# CHAIRCONTROLMOTORS.net
KiCad netlist of a schematic drawn in EAGLE
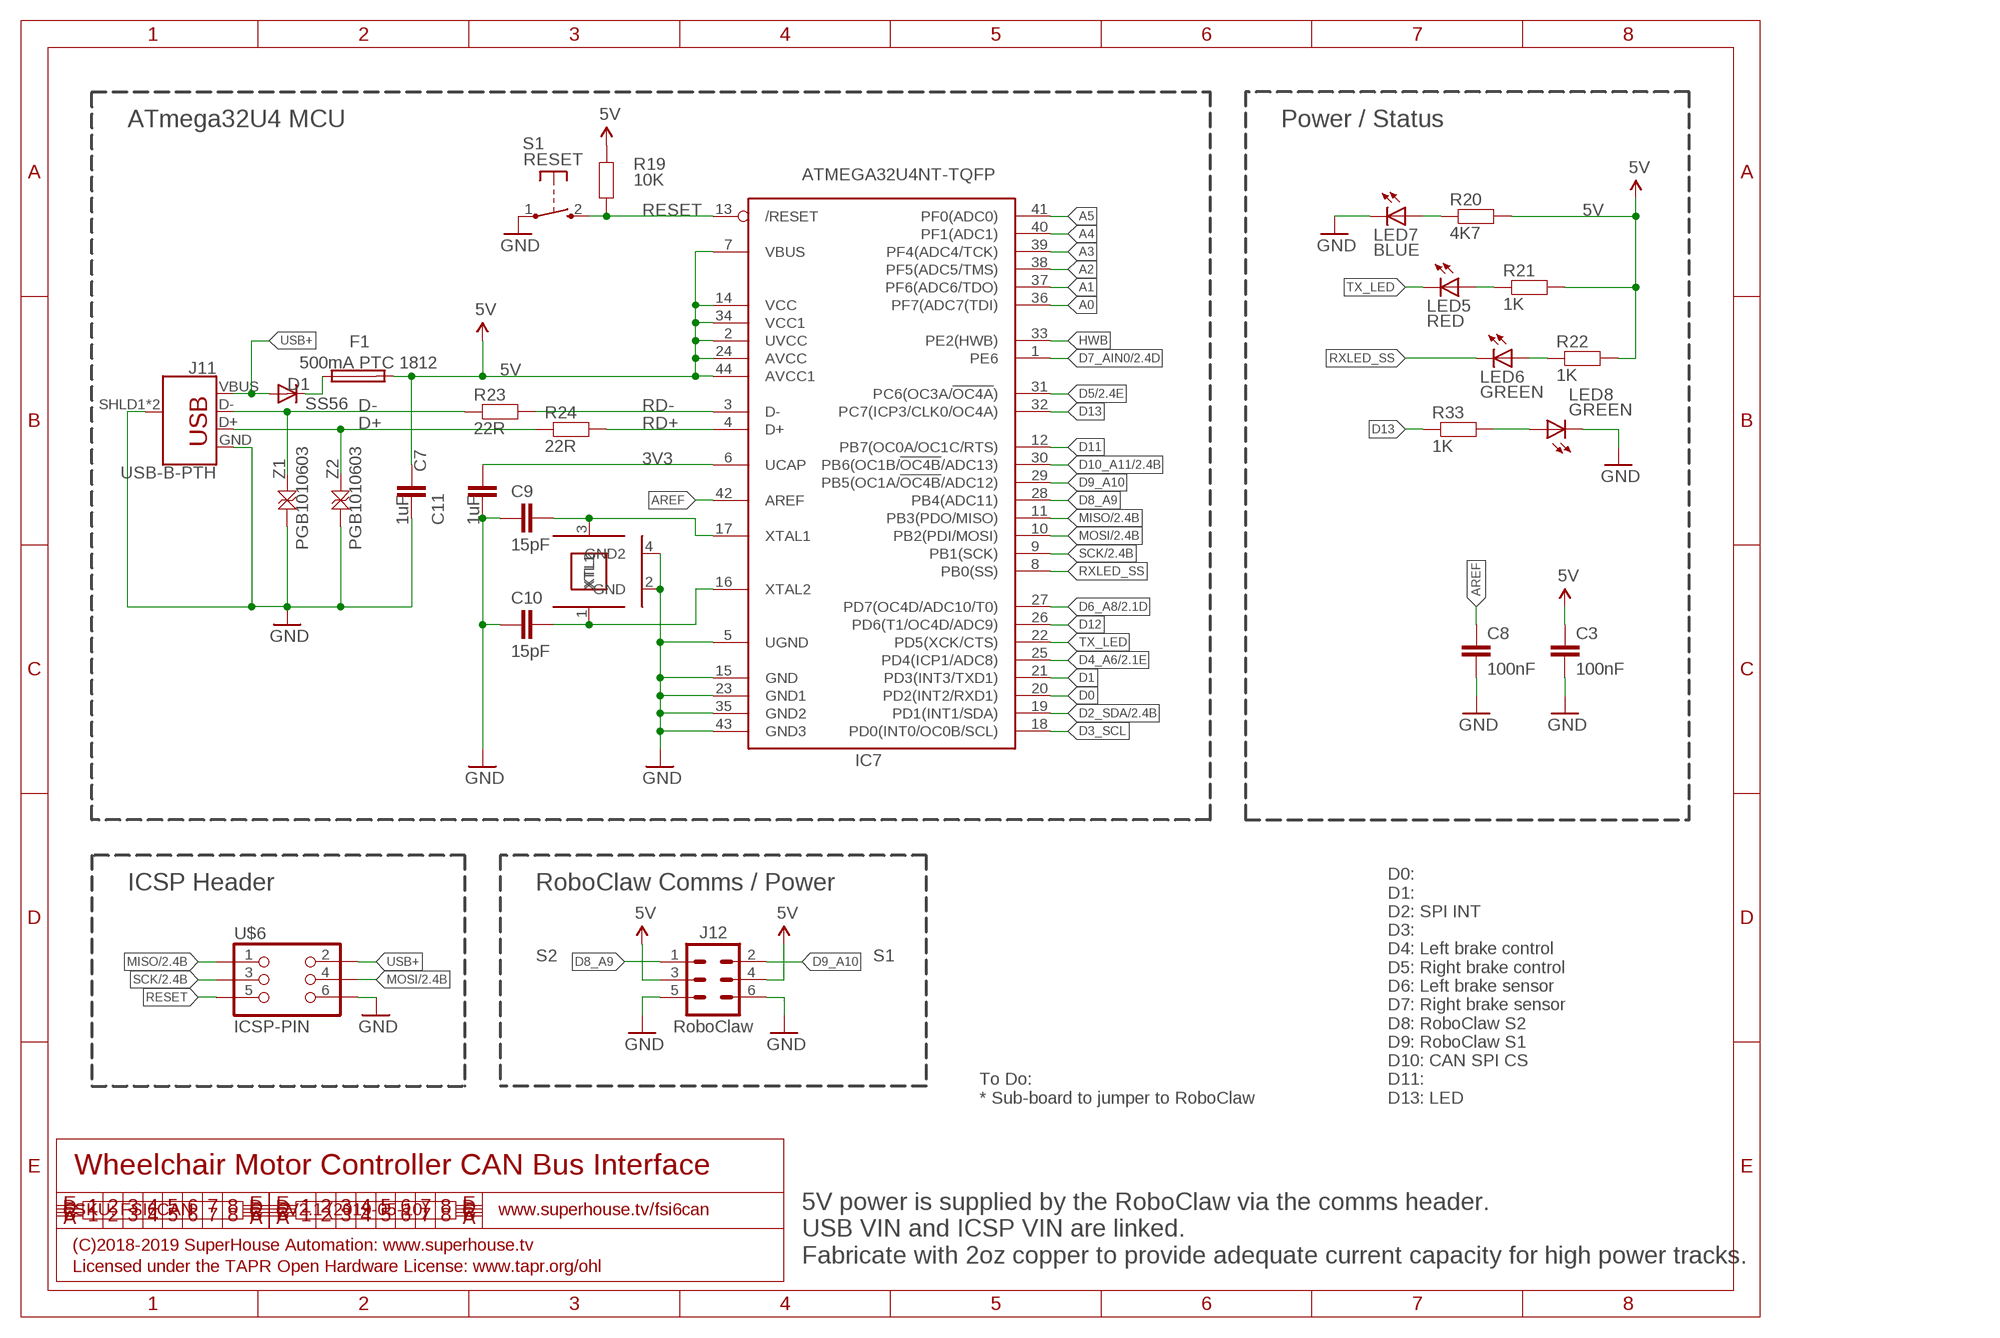
[diagram p0: schematic, sheet 1]
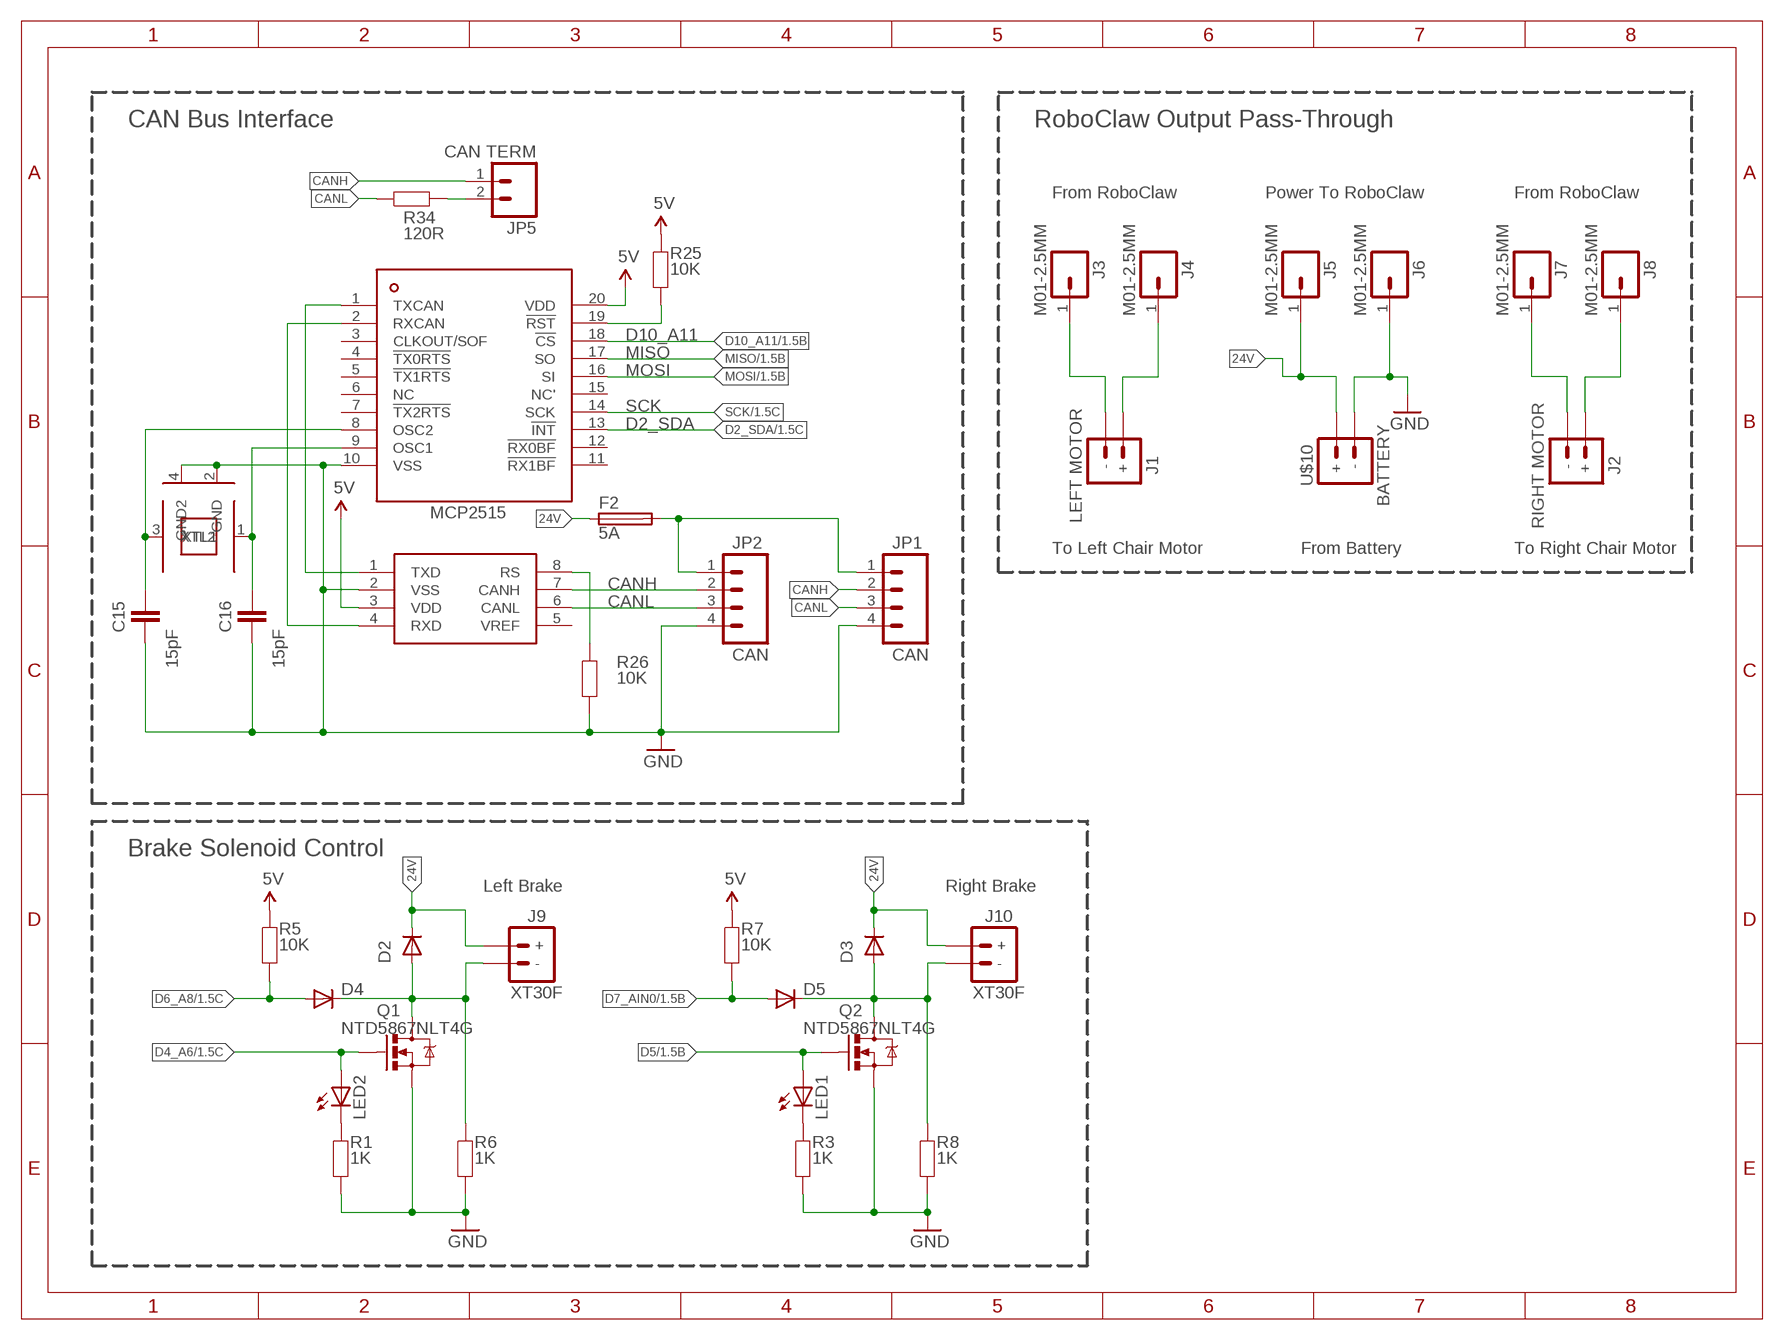
[diagram p1: schematic, sheet 2]

(export (version "E")
  (design (tool "Eeschema 10.0.6"))
  (components
    (comp (ref "C15")
      (value "15pF")
      (footprint "eagle-import:C0603")
      (libsource (lib "eagle-import") (part "CAP0603"))
    )
    (comp (ref "C16")
      (value "15pF")
      (footprint "eagle-import:C0603")
      (libsource (lib "eagle-import") (part "CAP0603"))
    )
    (comp (ref "D2")
      (value "DIODESMA")
      (footprint "eagle-import:SMA-DIODE")
      (libsource (lib "eagle-import") (part "DIODESMA"))
    )
    (comp (ref "D3")
      (value "DIODESMA")
      (footprint "eagle-import:SMA-DIODE")
      (libsource (lib "eagle-import") (part "DIODESMA"))
    )
    (comp (ref "D4")
      (value "DIODESOD")
      (footprint "eagle-import:SOD-323")
      (libsource (lib "eagle-import") (part "DIODESOD"))
    )
    (comp (ref "D5")
      (value "DIODESOD")
      (footprint "eagle-import:SOD-323")
      (libsource (lib "eagle-import") (part "DIODESOD"))
    )
    (comp (ref "F2")
      (value "5A")
      (footprint "eagle-import:MCCQ-122")
      (libsource (lib "eagle-import") (part "FUSE"))
    )
    (comp (ref "IC5")
      (value "MCP2551")
      (footprint "eagle-import:SO08")
      (libsource (lib "eagle-import") (part "MCP2551"))
    )
    (comp (ref "IC6")
      (value "MCP2515")
      (footprint "eagle-import:TSSOP20")
      (libsource (lib "eagle-import") (part "MCP2515"))
    )
    (comp (ref "J1")
      (value "LEFT MOTOR")
      (footprint "eagle-import:XT60PW-F")
      (libsource (lib "eagle-import") (part "XTXX-60F"))
    )
    (comp (ref "J2")
      (value "RIGHT MOTOR")
      (footprint "eagle-import:XT60PW-F")
      (libsource (lib "eagle-import") (part "XTXX-60F"))
    )
    (comp (ref "J3")
      (value "M01-2.5MM")
      (footprint "eagle-import:1X01-2.5MM")
      (libsource (lib "eagle-import") (part "M01-2.5MM"))
    )
    (comp (ref "J4")
      (value "M01-2.5MM")
      (footprint "eagle-import:1X01-2.5MM")
      (libsource (lib "eagle-import") (part "M01-2.5MM"))
    )
    (comp (ref "J5")
      (value "M01-2.5MM")
      (footprint "eagle-import:1X01-2.5MM")
      (libsource (lib "eagle-import") (part "M01-2.5MM"))
    )
    (comp (ref "J6")
      (value "M01-2.5MM")
      (footprint "eagle-import:1X01-2.5MM")
      (libsource (lib "eagle-import") (part "M01-2.5MM"))
    )
    (comp (ref "J7")
      (value "M01-2.5MM")
      (footprint "eagle-import:1X01-2.5MM")
      (libsource (lib "eagle-import") (part "M01-2.5MM"))
    )
    (comp (ref "J8")
      (value "M01-2.5MM")
      (footprint "eagle-import:1X01-2.5MM")
      (libsource (lib "eagle-import") (part "M01-2.5MM"))
    )
    (comp (ref "J9")
      (value "XT30F")
      (footprint "eagle-import:XT30PW-F")
      (libsource (lib "eagle-import") (part "XTXX-30F"))
    )
    (comp (ref "J10")
      (value "XT30F")
      (footprint "eagle-import:XT30PW-F")
      (libsource (lib "eagle-import") (part "XTXX-30F"))
    )
    (comp (ref "JP1")
      (value "CAN")
      (footprint "eagle-import:1X04-P")
      (libsource (lib "eagle-import") (part "M04-PIN"))
    )
    (comp (ref "JP2")
      (value "CAN")
      (footprint "eagle-import:1X04-P")
      (libsource (lib "eagle-import") (part "M04-PIN"))
    )
    (comp (ref "JP5")
      (value "CAN TERM")
      (footprint "eagle-import:1X02-P")
      (libsource (lib "eagle-import") (part "M02-PIN"))
    )
    (comp (ref "LED1")
      (value "LED0603")
      (footprint "eagle-import:LED-0603")
      (libsource (lib "eagle-import") (part "LED0603"))
    )
    (comp (ref "LED2")
      (value "LED0603")
      (footprint "eagle-import:LED-0603")
      (libsource (lib "eagle-import") (part "LED0603"))
    )
    (comp (ref "Q1")
      (value "NTD5867NLT4G")
      (footprint "eagle-import:DPACK")
      (libsource (lib "eagle-import") (part "MOSFET-NCHANNEL-DPAK"))
    )
    (comp (ref "Q2")
      (value "NTD5867NLT4G")
      (footprint "eagle-import:DPACK")
      (libsource (lib "eagle-import") (part "MOSFET-NCHANNEL-DPAK"))
    )
    (comp (ref "R1")
      (value "1K")
      (footprint "eagle-import:R0603")
      (libsource (lib "eagle-import") (part "RESISTOR0603"))
    )
    (comp (ref "R3")
      (value "1K")
      (footprint "eagle-import:R0603")
      (libsource (lib "eagle-import") (part "RESISTOR0603"))
    )
    (comp (ref "R5")
      (value "10K")
      (footprint "eagle-import:R0603")
      (libsource (lib "eagle-import") (part "RESISTOR0603"))
    )
    (comp (ref "R6")
      (value "1K")
      (footprint "eagle-import:R0603")
      (libsource (lib "eagle-import") (part "RESISTOR0603"))
    )
    (comp (ref "R7")
      (value "10K")
      (footprint "eagle-import:R0603")
      (libsource (lib "eagle-import") (part "RESISTOR0603"))
    )
    (comp (ref "R8")
      (value "1K")
      (footprint "eagle-import:R0603")
      (libsource (lib "eagle-import") (part "RESISTOR0603"))
    )
    (comp (ref "R25")
      (value "10K")
      (footprint "eagle-import:R0603")
      (libsource (lib "eagle-import") (part "RESISTOR0603"))
    )
    (comp (ref "R26")
      (value "10K")
      (footprint "eagle-import:R0603")
      (libsource (lib "eagle-import") (part "RESISTOR0603"))
    )
    (comp (ref "R34")
      (value "120R")
      (footprint "eagle-import:R0603")
      (libsource (lib "eagle-import") (part "RESISTOR0603"))
    )
    (comp (ref "U$10")
      (value "BATTERY")
      (footprint "eagle-import:XT90PW-M")
      (libsource (lib "eagle-import") (part "XTXX-90M"))
    )
    (comp (ref "XTL4")
      (value "16MHz")
      (footprint "eagle-import:CRYSTAL-SMD-3X2")
      (libsource (lib "eagle-import") (part "CRYSTAL-GND3X2"))
    )
    (comp (ref "C3")
      (value "100nF")
      (footprint "eagle-import:C0603")
      (libsource (lib "eagle-import") (part "CAP0603"))
    )
    (comp (ref "C7")
      (value "1uF")
      (footprint "eagle-import:C0603")
      (libsource (lib "eagle-import") (part "CAP0603"))
    )
    (comp (ref "C8")
      (value "100nF")
      (footprint "eagle-import:C0603")
      (libsource (lib "eagle-import") (part "CAP0603"))
    )
    (comp (ref "C9")
      (value "15pF")
      (footprint "eagle-import:C0603")
      (libsource (lib "eagle-import") (part "CAP0603"))
    )
    (comp (ref "C10")
      (value "15pF")
      (footprint "eagle-import:C0603")
      (libsource (lib "eagle-import") (part "CAP0603"))
    )
    (comp (ref "C11")
      (value "1uF")
      (footprint "eagle-import:C0603")
      (libsource (lib "eagle-import") (part "CAP0603"))
    )
    (comp (ref "D1")
      (value "SS56")
      (footprint "eagle-import:SMA-DIODE")
      (libsource (lib "eagle-import") (part "DIODESMA"))
    )
    (comp (ref "F1")
      (value "500mA PTC 1812")
      (footprint "eagle-import:1812")
      (libsource (lib "eagle-import") (part "PTC050"))
    )
    (comp (ref "IC7")
      (value "ATMEGA32U4NT-TQFP")
      (footprint "eagle-import:TQFP44")
      (libsource (lib "eagle-import") (part "ATMEGA32U4NT-TQFP"))
    )
    (comp (ref "J11")
      (value "USB-B-PTH")
      (footprint "eagle-import:USB-B-PTH")
      (libsource (lib "eagle-import") (part "USB-B-PTH"))
    )
    (comp (ref "J12")
      (value "RoboClaw")
      (footprint "eagle-import:2X03-P")
      (libsource (lib "eagle-import") (part "M02X3-PIN"))
    )
    (comp (ref "LED5")
      (value "RED")
      (footprint "eagle-import:LED-0603")
      (libsource (lib "eagle-import") (part "LED0603"))
    )
    (comp (ref "LED6")
      (value "GREEN")
      (footprint "eagle-import:LED-0603")
      (libsource (lib "eagle-import") (part "LED0603"))
    )
    (comp (ref "LED7")
      (value "BLUE")
      (footprint "eagle-import:LED-0603")
      (libsource (lib "eagle-import") (part "LED0603"))
    )
    (comp (ref "LED8")
      (value "GREEN")
      (footprint "eagle-import:LED-0603")
      (libsource (lib "eagle-import") (part "LED0603"))
    )
    (comp (ref "R19")
      (value "10K")
      (footprint "eagle-import:R0603")
      (libsource (lib "eagle-import") (part "RESISTOR0603"))
    )
    (comp (ref "R20")
      (value "4K7")
      (footprint "eagle-import:R0603")
      (libsource (lib "eagle-import") (part "RESISTOR0603"))
    )
    (comp (ref "R21")
      (value "1K")
      (footprint "eagle-import:R0603")
      (libsource (lib "eagle-import") (part "RESISTOR0603"))
    )
    (comp (ref "R22")
      (value "1K")
      (footprint "eagle-import:R0603")
      (libsource (lib "eagle-import") (part "RESISTOR0603"))
    )
    (comp (ref "R23")
      (value "22R")
      (footprint "eagle-import:R0603")
      (libsource (lib "eagle-import") (part "RESISTOR0603"))
    )
    (comp (ref "R24")
      (value "22R")
      (footprint "eagle-import:R0603")
      (libsource (lib "eagle-import") (part "RESISTOR0603"))
    )
    (comp (ref "R33")
      (value "1K")
      (footprint "eagle-import:R0603")
      (libsource (lib "eagle-import") (part "RESISTOR0603"))
    )
    (comp (ref "S1")
      (value "RESET")
      (footprint "eagle-import:TACTILE_SMT_3X4X2")
      (libsource (lib "eagle-import") (part "TAC_SWITCH_2PINSMT"))
    )
    (comp (ref "U$6")
      (value "ICSP-PIN")
      (footprint "eagle-import:2X03-ICSP")
      (libsource (lib "eagle-import") (part "ICSP-PIN"))
    )
    (comp (ref "XTL2")
      (value "16MHz")
      (footprint "eagle-import:CRYSTAL-SMD-3X2")
      (libsource (lib "eagle-import") (part "CRYSTAL-GND3X2"))
    )
    (comp (ref "Z1")
      (value "PGB1010603")
      (footprint "eagle-import:TVS0603")
      (libsource (lib "eagle-import") (part "TVS0603"))
    )
    (comp (ref "Z2")
      (value "PGB1010603")
      (footprint "eagle-import:TVS0603")
      (libsource (lib "eagle-import") (part "TVS0603"))
    )
  )
  (nets
    (net (code "1") (name "3V3") (class "Default")
      (node (ref "C11") (pin "2") (pinfunction "2_2") (pintype "passive"))
      (node (ref "IC7") (pin "6") (pinfunction "UCAP_6") (pintype "bidirectional"))
    )
    (net (code "2") (name "5V") (class "Default")
      (node (ref "C3") (pin "1") (pinfunction "1_1") (pintype "passive"))
      (node (ref "C7") (pin "1") (pinfunction "1_1") (pintype "passive"))
      (node (ref "F1") (pin "2") (pinfunction "2_2") (pintype "passive"))
      (node (ref "IC5") (pin "3") (pinfunction "VDD_3") (pintype "bidirectional"))
      (node (ref "IC6") (pin "20") (pinfunction "VDD_20") (pintype "bidirectional"))
      (node (ref "IC7") (pin "14") (pinfunction "VCC_14") (pintype "bidirectional"))
      (node (ref "IC7") (pin "2") (pinfunction "UVCC_2") (pintype "bidirectional"))
      (node (ref "IC7") (pin "24") (pinfunction "AVCC_24") (pintype "bidirectional"))
      (node (ref "IC7") (pin "34") (pinfunction "VCC1_34") (pintype "bidirectional"))
      (node (ref "IC7") (pin "44") (pinfunction "AVCC1_44") (pintype "bidirectional"))
      (node (ref "IC7") (pin "7") (pinfunction "VBUS_7") (pintype "bidirectional"))
      (node (ref "J12") (pin "3") (pinfunction "3_3") (pintype "passive"))
      (node (ref "J12") (pin "4") (pinfunction "4_4") (pintype "passive"))
      (node (ref "R19") (pin "2") (pinfunction "2_2") (pintype "passive"))
      (node (ref "R20") (pin "2") (pinfunction "2_2") (pintype "passive"))
      (node (ref "R21") (pin "2") (pinfunction "2_2") (pintype "passive"))
      (node (ref "R22") (pin "2") (pinfunction "2_2") (pintype "passive"))
      (node (ref "R25") (pin "2") (pinfunction "2_2") (pintype "passive"))
      (node (ref "R5") (pin "2") (pinfunction "2_2") (pintype "passive"))
      (node (ref "R7") (pin "2") (pinfunction "2_2") (pintype "passive"))
    )
    (net (code "3") (name "24V") (class "Default")
      (node (ref "D2") (pin "C") (pinfunction "C_C") (pintype "passive"))
      (node (ref "D3") (pin "C") (pinfunction "C_C") (pintype "passive"))
      (node (ref "F2") (pin "1") (pinfunction "1_1") (pintype "passive"))
      (node (ref "F2") (pin "2") (pinfunction "1_2") (pintype "passive"))
      (node (ref "J10") (pin "+") (pinfunction "+_+") (pintype "passive"))
      (node (ref "J5") (pin "1") (pinfunction "1_1") (pintype "passive"))
      (node (ref "J9") (pin "+") (pinfunction "+_+") (pintype "passive"))
      (node (ref "U$10") (pin "+") (pinfunction "+_+") (pintype "passive"))
    )
    (net (code "4") (name "A0") (class "Default")
      (node (ref "IC7") (pin "36") (pinfunction "PF7(ADC7(TDI)_36") (pintype "bidirectional"))
    )
    (net (code "5") (name "A1") (class "Default")
      (node (ref "IC7") (pin "37") (pinfunction "PF6(ADC6/TDO)_37") (pintype "bidirectional"))
    )
    (net (code "6") (name "A2") (class "Default")
      (node (ref "IC7") (pin "38") (pinfunction "PF5(ADC5/TMS)_38") (pintype "bidirectional"))
    )
    (net (code "7") (name "A3") (class "Default")
      (node (ref "IC7") (pin "39") (pinfunction "PF4(ADC4/TCK)_39") (pintype "bidirectional"))
    )
    (net (code "8") (name "A4") (class "Default")
      (node (ref "IC7") (pin "40") (pinfunction "PF1(ADC1)_40") (pintype "bidirectional"))
    )
    (net (code "9") (name "A5") (class "Default")
      (node (ref "IC7") (pin "41") (pinfunction "PF0(ADC0)_41") (pintype "bidirectional"))
    )
    (net (code "10") (name "AREF") (class "Default")
      (node (ref "C8") (pin "1") (pinfunction "1_1") (pintype "passive"))
      (node (ref "IC7") (pin "42") (pinfunction "AREF_42") (pintype "bidirectional"))
    )
    (net (code "11") (name "CANH") (class "Default")
      (node (ref "IC5") (pin "7") (pinfunction "CANH_7") (pintype "bidirectional"))
      (node (ref "JP1") (pin "2") (pinfunction "2_2") (pintype "passive"))
      (node (ref "JP2") (pin "2") (pinfunction "2_2") (pintype "passive"))
      (node (ref "JP5") (pin "1") (pinfunction "1_1") (pintype "passive"))
    )
    (net (code "12") (name "CANL") (class "Default")
      (node (ref "IC5") (pin "6") (pinfunction "CANL_6") (pintype "bidirectional"))
      (node (ref "JP1") (pin "3") (pinfunction "3_3") (pintype "passive"))
      (node (ref "JP2") (pin "3") (pinfunction "3_3") (pintype "passive"))
      (node (ref "R34") (pin "1") (pinfunction "1_1") (pintype "passive"))
    )
    (net (code "13") (name "D+") (class "Default")
      (node (ref "J11") (pin "D+") (pinfunction "D+_D+") (pintype "bidirectional"))
      (node (ref "R24") (pin "1") (pinfunction "1_1") (pintype "passive"))
      (node (ref "Z2") (pin "2") (pinfunction "2_2") (pintype "passive"))
    )
    (net (code "14") (name "D-") (class "Default")
      (node (ref "J11") (pin "D-") (pinfunction "D-_D-") (pintype "bidirectional"))
      (node (ref "R23") (pin "1") (pinfunction "1_1") (pintype "passive"))
      (node (ref "Z1") (pin "2") (pinfunction "2_2") (pintype "passive"))
    )
    (net (code "15") (name "D0") (class "Default")
      (node (ref "IC7") (pin "20") (pinfunction "PD2(INT2/RXD1)_20") (pintype "bidirectional"))
    )
    (net (code "16") (name "D1") (class "Default")
      (node (ref "IC7") (pin "21") (pinfunction "PD3(INT3/TXD1)_21") (pintype "bidirectional"))
    )
    (net (code "17") (name "D2_SDA") (class "Default")
      (node (ref "IC6") (pin "13") (pinfunction "~{INT}_13") (pintype "bidirectional"))
      (node (ref "IC7") (pin "19") (pinfunction "PD1(INT1/SDA)_19") (pintype "bidirectional"))
    )
    (net (code "18") (name "D3_SCL") (class "Default")
      (node (ref "IC7") (pin "18") (pinfunction "PD0(INT0/OC0B/SCL)_18") (pintype "bidirectional"))
    )
    (net (code "19") (name "D4_A6") (class "Default")
      (node (ref "IC7") (pin "25") (pinfunction "PD4(ICP1/ADC8)_25") (pintype "bidirectional"))
      (node (ref "LED2") (pin "A") (pinfunction "A_A") (pintype "passive"))
      (node (ref "Q1") (pin "1") (pinfunction "G_1") (pintype "passive"))
    )
    (net (code "20") (name "D5") (class "Default")
      (node (ref "IC7") (pin "31") (pinfunction "PC6(OC3A/~{OC4A})_31") (pintype "bidirectional"))
      (node (ref "LED1") (pin "A") (pinfunction "A_A") (pintype "passive"))
      (node (ref "Q2") (pin "1") (pinfunction "G_1") (pintype "passive"))
    )
    (net (code "21") (name "D6_A8") (class "Default")
      (node (ref "D4") (pin "2") (pinfunction "A_2") (pintype "passive"))
      (node (ref "IC7") (pin "27") (pinfunction "PD7(OC4D/ADC10/T0)_27") (pintype "bidirectional"))
      (node (ref "R5") (pin "1") (pinfunction "1_1") (pintype "passive"))
    )
    (net (code "22") (name "D7_AIN0") (class "Default")
      (node (ref "D5") (pin "2") (pinfunction "A_2") (pintype "passive"))
      (node (ref "IC7") (pin "1") (pinfunction "PE6_1") (pintype "bidirectional"))
      (node (ref "R7") (pin "1") (pinfunction "1_1") (pintype "passive"))
    )
    (net (code "23") (name "D8_A9") (class "Default")
      (node (ref "IC7") (pin "28") (pinfunction "PB4(ADC11)_28") (pintype "bidirectional"))
      (node (ref "J12") (pin "1") (pinfunction "1_1") (pintype "passive"))
    )
    (net (code "24") (name "D9_A10") (class "Default")
      (node (ref "IC7") (pin "29") (pinfunction "PB5(OC1A/~{OC4B}/ADC12)_29") (pintype "bidirectional"))
      (node (ref "J12") (pin "2") (pinfunction "2_2") (pintype "passive"))
    )
    (net (code "25") (name "D10_A11") (class "Default")
      (node (ref "IC6") (pin "18") (pinfunction "~{CS}_18") (pintype "bidirectional"))
      (node (ref "IC7") (pin "30") (pinfunction "PB6(OC1B/~{OC4B}/ADC13)_30") (pintype "bidirectional"))
    )
    (net (code "26") (name "D11") (class "Default")
      (node (ref "IC7") (pin "12") (pinfunction "PB7(OC0A/OC1C/RTS)_12") (pintype "bidirectional"))
    )
    (net (code "27") (name "D12") (class "Default")
      (node (ref "IC7") (pin "26") (pinfunction "PD6(T1/OC4D/ADC9)_26") (pintype "bidirectional"))
    )
    (net (code "28") (name "D13") (class "Default")
      (node (ref "IC7") (pin "32") (pinfunction "PC7(ICP3/CLK0/OC4A)_32") (pintype "bidirectional"))
      (node (ref "R33") (pin "1") (pinfunction "1_1") (pintype "passive"))
    )
    (net (code "29") (name "GND") (class "Default")
      (node (ref "C10") (pin "1") (pinfunction "1_1") (pintype "passive"))
      (node (ref "C11") (pin "1") (pinfunction "1_1") (pintype "passive"))
      (node (ref "C15") (pin "1") (pinfunction "1_1") (pintype "passive"))
      (node (ref "C16") (pin "1") (pinfunction "1_1") (pintype "passive"))
      (node (ref "C3") (pin "2") (pinfunction "2_2") (pintype "passive"))
      (node (ref "C7") (pin "2") (pinfunction "2_2") (pintype "passive"))
      (node (ref "C8") (pin "2") (pinfunction "2_2") (pintype "passive"))
      (node (ref "C9") (pin "1") (pinfunction "1_1") (pintype "passive"))
      (node (ref "IC5") (pin "2") (pinfunction "VSS_2") (pintype "bidirectional"))
      (node (ref "IC6") (pin "10") (pinfunction "VSS_10") (pintype "bidirectional"))
      (node (ref "IC7") (pin "15") (pinfunction "GND_15") (pintype "bidirectional"))
      (node (ref "IC7") (pin "23") (pinfunction "GND1_23") (pintype "bidirectional"))
      (node (ref "IC7") (pin "35") (pinfunction "GND2_35") (pintype "bidirectional"))
      (node (ref "IC7") (pin "43") (pinfunction "GND3_43") (pintype "bidirectional"))
      (node (ref "IC7") (pin "5") (pinfunction "UGND_5") (pintype "bidirectional"))
      (node (ref "J11") (pin "GND") (pinfunction "GND_GND") (pintype "power_in"))
      (node (ref "J11") (pin "SHLD1") (pinfunction "SHIELD_SHLD1") (pintype "bidirectional"))
      (node (ref "J11") (pin "SHLD2") (pinfunction "SHIELD_SHLD2") (pintype "bidirectional"))
      (node (ref "J12") (pin "5") (pinfunction "5_5") (pintype "passive"))
      (node (ref "J12") (pin "6") (pinfunction "6_6") (pintype "passive"))
      (node (ref "J6") (pin "1") (pinfunction "1_1") (pintype "passive"))
      (node (ref "JP1") (pin "4") (pinfunction "4_4") (pintype "passive"))
      (node (ref "JP2") (pin "4") (pinfunction "4_4") (pintype "passive"))
      (node (ref "LED7") (pin "C") (pinfunction "C_C") (pintype "passive"))
      (node (ref "LED8") (pin "C") (pinfunction "C_C") (pintype "passive"))
      (node (ref "Q1") (pin "3") (pinfunction "S_3") (pintype "passive"))
      (node (ref "Q2") (pin "3") (pinfunction "S_3") (pintype "passive"))
      (node (ref "R1") (pin "1") (pinfunction "1_1") (pintype "passive"))
      (node (ref "R26") (pin "1") (pinfunction "1_1") (pintype "passive"))
      (node (ref "R3") (pin "1") (pinfunction "1_1") (pintype "passive"))
      (node (ref "R6") (pin "1") (pinfunction "1_1") (pintype "passive"))
      (node (ref "R8") (pin "1") (pinfunction "1_1") (pintype "passive"))
      (node (ref "S1") (pin "1") (pinfunction "P_1") (pintype "passive"))
      (node (ref "U$10") (pin "-") (pinfunction "-_-") (pintype "passive"))
      (node (ref "U$6") (pin "6") (pinfunction "6_6") (pintype "passive"))
      (node (ref "XTL2") (pin "2") (pinfunction "GND_2") (pintype "bidirectional"))
      (node (ref "XTL2") (pin "4") (pinfunction "GND2_4") (pintype "bidirectional"))
      (node (ref "XTL4") (pin "2") (pinfunction "GND_2") (pintype "bidirectional"))
      (node (ref "XTL4") (pin "4") (pinfunction "GND2_4") (pintype "bidirectional"))
      (node (ref "Z1") (pin "1") (pinfunction "1_1") (pintype "passive"))
      (node (ref "Z2") (pin "1") (pinfunction "1_1") (pintype "passive"))
    )
    (net (code "30") (name "HWB") (class "Default")
      (node (ref "IC7") (pin "33") (pinfunction "PE2(HWB)_33") (pintype "bidirectional"))
    )
    (net (code "31") (name "MISO") (class "Default")
      (node (ref "IC6") (pin "17") (pinfunction "SO_17") (pintype "bidirectional"))
      (node (ref "IC7") (pin "11") (pinfunction "PB3(PDO/MISO)_11") (pintype "bidirectional"))
      (node (ref "U$6") (pin "1") (pinfunction "1_1") (pintype "passive"))
    )
    (net (code "32") (name "MOSI") (class "Default")
      (node (ref "IC6") (pin "16") (pinfunction "SI_16") (pintype "bidirectional"))
      (node (ref "IC7") (pin "10") (pinfunction "PB2(PDI/MOSI)_10") (pintype "bidirectional"))
      (node (ref "U$6") (pin "4") (pinfunction "4_4") (pintype "passive"))
    )
    (net (code "33") (name "Net-(D1-PadC)") (class "Default")
      (node (ref "D1") (pin "C") (pinfunction "C_C") (pintype "passive"))
      (node (ref "F1") (pin "1") (pinfunction "1_1") (pintype "passive"))
    )
    (net (code "34") (name "Net-(D4-C)") (class "Default")
      (node (ref "D2") (pin "A") (pinfunction "A_A") (pintype "passive"))
      (node (ref "D4") (pin "1") (pinfunction "C_1") (pintype "passive"))
      (node (ref "J9") (pin "-") (pinfunction "-_-") (pintype "passive"))
      (node (ref "Q1") (pin "2") (pinfunction "D_2") (pintype "passive"))
      (node (ref "R6") (pin "2") (pinfunction "2_2") (pintype "passive"))
    )
    (net (code "35") (name "Net-(D5-C)") (class "Default")
      (node (ref "D3") (pin "A") (pinfunction "A_A") (pintype "passive"))
      (node (ref "D5") (pin "1") (pinfunction "C_1") (pintype "passive"))
      (node (ref "J10") (pin "-") (pinfunction "-_-") (pintype "passive"))
      (node (ref "Q2") (pin "2") (pinfunction "D_2") (pintype "passive"))
      (node (ref "R8") (pin "2") (pinfunction "2_2") (pintype "passive"))
    )
    (net (code "36") (name "Net-(F2-2-Pad3)") (class "Default")
      (node (ref "F2") (pin "3") (pinfunction "2_3") (pintype "passive"))
      (node (ref "F2") (pin "4") (pinfunction "2_4") (pintype "passive"))
      (node (ref "JP1") (pin "1") (pinfunction "1_1") (pintype "passive"))
      (node (ref "JP2") (pin "1") (pinfunction "1_1") (pintype "passive"))
    )
    (net (code "37") (name "Net-(IC5-RS)") (class "Default")
      (node (ref "IC5") (pin "8") (pinfunction "RS_8") (pintype "bidirectional"))
      (node (ref "R26") (pin "2") (pinfunction "2_2") (pintype "passive"))
    )
    (net (code "38") (name "Net-(IC5-RXD)") (class "Default")
      (node (ref "IC5") (pin "4") (pinfunction "RXD_4") (pintype "bidirectional"))
      (node (ref "IC6") (pin "2") (pinfunction "RXCAN_2") (pintype "bidirectional"))
    )
    (net (code "39") (name "Net-(IC5-TXD)") (class "Default")
      (node (ref "IC5") (pin "1") (pinfunction "TXD_1") (pintype "bidirectional"))
      (node (ref "IC6") (pin "1") (pinfunction "TXCAN_1") (pintype "bidirectional"))
    )
    (net (code "40") (name "Net-(IC6-OSC1)") (class "Default")
      (node (ref "C16") (pin "2") (pinfunction "2_2") (pintype "passive"))
      (node (ref "IC6") (pin "9") (pinfunction "OSC1_9") (pintype "bidirectional"))
      (node (ref "XTL4") (pin "1") (pinfunction "XTL1_1") (pintype "bidirectional"))
    )
    (net (code "41") (name "Net-(IC6-OSC2)") (class "Default")
      (node (ref "C15") (pin "2") (pinfunction "2_2") (pintype "passive"))
      (node (ref "IC6") (pin "8") (pinfunction "OSC2_8") (pintype "bidirectional"))
      (node (ref "XTL4") (pin "3") (pinfunction "XTL2_3") (pintype "bidirectional"))
    )
    (net (code "42") (name "Net-(IC6-~{RST})") (class "Default")
      (node (ref "IC6") (pin "19") (pinfunction "~{RST}_19") (pintype "bidirectional"))
      (node (ref "R25") (pin "1") (pinfunction "1_1") (pintype "passive"))
    )
    (net (code "43") (name "Net-(IC7-XTAL1)") (class "Default")
      (node (ref "C9") (pin "2") (pinfunction "2_2") (pintype "passive"))
      (node (ref "IC7") (pin "17") (pinfunction "XTAL1_17") (pintype "bidirectional"))
      (node (ref "XTL2") (pin "3") (pinfunction "XTL2_3") (pintype "bidirectional"))
    )
    (net (code "44") (name "Net-(IC7-XTAL2)") (class "Default")
      (node (ref "C10") (pin "2") (pinfunction "2_2") (pintype "passive"))
      (node (ref "IC7") (pin "16") (pinfunction "XTAL2_16") (pintype "bidirectional"))
      (node (ref "XTL2") (pin "1") (pinfunction "XTL1_1") (pintype "bidirectional"))
    )
    (net (code "45") (name "Net-(J1-Pad+)") (class "Default")
      (node (ref "J1") (pin "+") (pinfunction "+_+") (pintype "passive"))
      (node (ref "J4") (pin "1") (pinfunction "1_1") (pintype "passive"))
    )
    (net (code "46") (name "Net-(J1-Pad-)") (class "Default")
      (node (ref "J1") (pin "-") (pinfunction "-_-") (pintype "passive"))
      (node (ref "J3") (pin "1") (pinfunction "1_1") (pintype "passive"))
    )
    (net (code "47") (name "Net-(J2-Pad+)") (class "Default")
      (node (ref "J2") (pin "+") (pinfunction "+_+") (pintype "passive"))
      (node (ref "J8") (pin "1") (pinfunction "1_1") (pintype "passive"))
    )
    (net (code "48") (name "Net-(J2-Pad-)") (class "Default")
      (node (ref "J2") (pin "-") (pinfunction "-_-") (pintype "passive"))
      (node (ref "J7") (pin "1") (pinfunction "1_1") (pintype "passive"))
    )
    (net (code "49") (name "Net-(JP5-Pad2)") (class "Default")
      (node (ref "JP5") (pin "2") (pinfunction "2_2") (pintype "passive"))
      (node (ref "R34") (pin "2") (pinfunction "2_2") (pintype "passive"))
    )
    (net (code "50") (name "Net-(LED1-PadC)") (class "Default")
      (node (ref "LED1") (pin "C") (pinfunction "C_C") (pintype "passive"))
      (node (ref "R3") (pin "2") (pinfunction "2_2") (pintype "passive"))
    )
    (net (code "51") (name "Net-(LED2-PadC)") (class "Default")
      (node (ref "LED2") (pin "C") (pinfunction "C_C") (pintype "passive"))
      (node (ref "R1") (pin "2") (pinfunction "2_2") (pintype "passive"))
    )
    (net (code "52") (name "Net-(LED5-PadA)") (class "Default")
      (node (ref "LED5") (pin "A") (pinfunction "A_A") (pintype "passive"))
      (node (ref "R21") (pin "1") (pinfunction "1_1") (pintype "passive"))
    )
    (net (code "53") (name "Net-(LED6-PadA)") (class "Default")
      (node (ref "LED6") (pin "A") (pinfunction "A_A") (pintype "passive"))
      (node (ref "R22") (pin "1") (pinfunction "1_1") (pintype "passive"))
    )
    (net (code "54") (name "Net-(LED7-PadA)") (class "Default")
      (node (ref "LED7") (pin "A") (pinfunction "A_A") (pintype "passive"))
      (node (ref "R20") (pin "1") (pinfunction "1_1") (pintype "passive"))
    )
    (net (code "55") (name "Net-(LED8-PadA)") (class "Default")
      (node (ref "LED8") (pin "A") (pinfunction "A_A") (pintype "passive"))
      (node (ref "R33") (pin "2") (pinfunction "2_2") (pintype "passive"))
    )
    (net (code "56") (name "RD+") (class "Default")
      (node (ref "IC7") (pin "4") (pinfunction "D+_4") (pintype "bidirectional"))
      (node (ref "R24") (pin "2") (pinfunction "2_2") (pintype "passive"))
    )
    (net (code "57") (name "RD-") (class "Default")
      (node (ref "IC7") (pin "3") (pinfunction "D-_3") (pintype "bidirectional"))
      (node (ref "R23") (pin "2") (pinfunction "2_2") (pintype "passive"))
    )
    (net (code "58") (name "RESET") (class "Default")
      (node (ref "IC7") (pin "13") (pinfunction "/RESET_13") (pintype "bidirectional"))
      (node (ref "R19") (pin "1") (pinfunction "1_1") (pintype "passive"))
      (node (ref "S1") (pin "2") (pinfunction "S_2") (pintype "passive"))
      (node (ref "U$6") (pin "5") (pinfunction "5_5") (pintype "passive"))
    )
    (net (code "59") (name "RXLED_SS") (class "Default")
      (node (ref "IC7") (pin "8") (pinfunction "PB0(SS)_8") (pintype "bidirectional"))
      (node (ref "LED6") (pin "C") (pinfunction "C_C") (pintype "passive"))
    )
    (net (code "60") (name "SCK") (class "Default")
      (node (ref "IC6") (pin "14") (pinfunction "SCK_14") (pintype "bidirectional"))
      (node (ref "IC7") (pin "9") (pinfunction "PB1(SCK)_9") (pintype "bidirectional"))
      (node (ref "U$6") (pin "3") (pinfunction "3_3") (pintype "passive"))
    )
    (net (code "61") (name "TX_LED") (class "Default")
      (node (ref "IC7") (pin "22") (pinfunction "PD5(XCK/CTS)_22") (pintype "bidirectional"))
      (node (ref "LED5") (pin "C") (pinfunction "C_C") (pintype "passive"))
    )
    (net (code "62") (name "USB+") (class "Default")
      (node (ref "D1") (pin "A") (pinfunction "A_A") (pintype "passive"))
      (node (ref "J11") (pin "VBUS") (pinfunction "VBUS_VBUS") (pintype "power_in"))
      (node (ref "U$6") (pin "2") (pinfunction "2_2") (pintype "passive"))
    )
    (net (code "63") (name "unconnected-(IC5-VREF-Pad5)") (class "Default")
      (node (ref "IC5") (pin "5") (pinfunction "VREF_5") (pintype "bidirectional"))
    )
    (net (code "64") (name "unconnected-(IC6-CLKOUT{slash}SOF-Pad3)") (class "Default")
      (node (ref "IC6") (pin "3") (pinfunction "CLKOUT/SOF_3") (pintype "bidirectional"))
    )
    (net (code "65") (name "unconnected-(IC6-NC'-Pad15)") (class "Default")
      (node (ref "IC6") (pin "15") (pinfunction "NC'_15") (pintype "bidirectional"))
    )
    (net (code "66") (name "unconnected-(IC6-NC-Pad6)") (class "Default")
      (node (ref "IC6") (pin "6") (pinfunction "NC_6") (pintype "bidirectional"))
    )
    (net (code "67") (name "unconnected-(IC6-~{RX0BF}-Pad12)") (class "Default")
      (node (ref "IC6") (pin "12") (pinfunction "~{RX0BF}_12") (pintype "bidirectional"))
    )
    (net (code "68") (name "unconnected-(IC6-~{RX1BF}-Pad11)") (class "Default")
      (node (ref "IC6") (pin "11") (pinfunction "~{RX1BF}_11") (pintype "bidirectional"))
    )
    (net (code "69") (name "unconnected-(IC6-~{TX0RTS}-Pad4)") (class "Default")
      (node (ref "IC6") (pin "4") (pinfunction "~{TX0RTS}_4") (pintype "bidirectional"))
    )
    (net (code "70") (name "unconnected-(IC6-~{TX1RTS}-Pad5)") (class "Default")
      (node (ref "IC6") (pin "5") (pinfunction "~{TX1RTS}_5") (pintype "bidirectional"))
    )
    (net (code "71") (name "unconnected-(IC6-~{TX2RTS}-Pad7)") (class "Default")
      (node (ref "IC6") (pin "7") (pinfunction "~{TX2RTS}_7") (pintype "bidirectional"))
    )
  )
)
